# max631.net
KiCad netlist of a schematic drawn in EAGLE
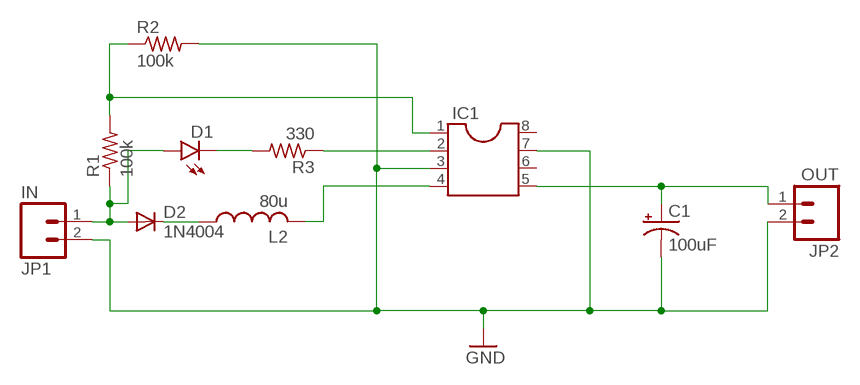
[diagram p0: schematic, sheet 1]

(export (version "E")
  (design (tool "Eeschema 10.0.6"))
  (components
    (comp (ref "C1")
      (value "100uF")
      (footprint "eagle-import:E2,5-5")
      (libsource (lib "eagle-import") (part "CPOL-USE2.5-5"))
    )
    (comp (ref "D1")
      (value "LED3MM")
      (footprint "eagle-import:LED3MM")
      (libsource (lib "eagle-import") (part "LED3MM"))
    )
    (comp (ref "D2")
      (value "1N4004")
      (footprint "eagle-import:DO41-10")
      (libsource (lib "eagle-import") (part "1N4004"))
    )
    (comp (ref "IC1")
      (value "DIL8")
      (footprint "eagle-import:DIL08")
      (libsource (lib "eagle-import") (part "DIL8"))
    )
    (comp (ref "JP1")
      (value "IN")
      (footprint "eagle-import:1X02_LOCK_LONGPADS")
      (libsource (lib "eagle-import") (part "M02LOCK_LONGPADS"))
    )
    (comp (ref "JP2")
      (value "OUT")
      (footprint "eagle-import:1X02_LOCK_LONGPADS")
      (libsource (lib "eagle-import") (part "M02LOCK_LONGPADS"))
    )
    (comp (ref "L2")
      (value "80u")
      (footprint "eagle-import:IR-2")
      (libsource (lib "eagle-import") (part "L-USIR-2"))
    )
    (comp (ref "R1")
      (value "100k")
      (footprint "eagle-import:0207_10")
      (libsource (lib "eagle-import") (part "R-US_0207/10"))
    )
    (comp (ref "R2")
      (value "100k")
      (footprint "eagle-import:0207_10")
      (libsource (lib "eagle-import") (part "R-US_0207/10"))
    )
    (comp (ref "R3")
      (value "330")
      (footprint "eagle-import:0207_10")
      (libsource (lib "eagle-import") (part "R-US_0207/10"))
    )
  )
  (nets
    (net (code "1") (name "GND") (class "Default")
      (node (ref "C1") (pin "-") (pinfunction "-_-") (pintype "passive"))
      (node (ref "IC1") (pin "3") (pinfunction "3_3") (pintype "passive"))
      (node (ref "IC1") (pin "7") (pinfunction "7_7") (pintype "passive"))
      (node (ref "JP1") (pin "2") (pinfunction "2_2") (pintype "passive"))
      (node (ref "JP2") (pin "2") (pinfunction "2_2") (pintype "passive"))
      (node (ref "R2") (pin "2") (pinfunction "2_2") (pintype "passive"))
    )
    (net (code "2") (name "Net-(C1-Pad+)") (class "Default")
      (node (ref "C1") (pin "+") (pinfunction "+_+") (pintype "passive"))
      (node (ref "IC1") (pin "5") (pinfunction "5_5") (pintype "passive"))
      (node (ref "JP2") (pin "1") (pinfunction "1_1") (pintype "passive"))
    )
    (net (code "3") (name "Net-(D1-C)") (class "Default")
      (node (ref "D1") (pin "K") (pinfunction "C_K") (pintype "passive"))
      (node (ref "R3") (pin "2") (pinfunction "2_2") (pintype "passive"))
    )
    (net (code "4") (name "Net-(D1-PadA)") (class "Default")
      (node (ref "D1") (pin "A") (pinfunction "A_A") (pintype "passive"))
      (node (ref "D2") (pin "A") (pinfunction "A_A") (pintype "passive"))
      (node (ref "JP1") (pin "1") (pinfunction "1_1") (pintype "passive"))
      (node (ref "R1") (pin "1") (pinfunction "1_1") (pintype "passive"))
    )
    (net (code "5") (name "Net-(D2-PadC)") (class "Default")
      (node (ref "D2") (pin "C") (pinfunction "C_C") (pintype "passive"))
      (node (ref "L2") (pin "1") (pinfunction "1_1") (pintype "passive"))
    )
    (net (code "6") (name "Net-(IC1-Pad1)") (class "Default")
      (node (ref "IC1") (pin "1") (pinfunction "1_1") (pintype "passive"))
      (node (ref "R1") (pin "2") (pinfunction "2_2") (pintype "passive"))
      (node (ref "R2") (pin "1") (pinfunction "1_1") (pintype "passive"))
    )
    (net (code "7") (name "Net-(IC1-Pad2)") (class "Default")
      (node (ref "IC1") (pin "2") (pinfunction "2_2") (pintype "passive"))
      (node (ref "R3") (pin "1") (pinfunction "1_1") (pintype "passive"))
    )
    (net (code "8") (name "Net-(IC1-Pad4)") (class "Default")
      (node (ref "IC1") (pin "4") (pinfunction "4_4") (pintype "passive"))
      (node (ref "L2") (pin "2") (pinfunction "2_2") (pintype "passive"))
    )
    (net (code "9") (name "unconnected-(IC1-Pad6)") (class "Default")
      (node (ref "IC1") (pin "6") (pinfunction "6_6") (pintype "passive"))
    )
    (net (code "10") (name "unconnected-(IC1-Pad8)") (class "Default")
      (node (ref "IC1") (pin "8") (pinfunction "8_8") (pintype "passive"))
    )
  )
)
